# untitled.net
KiCad netlist of a schematic drawn in EAGLE
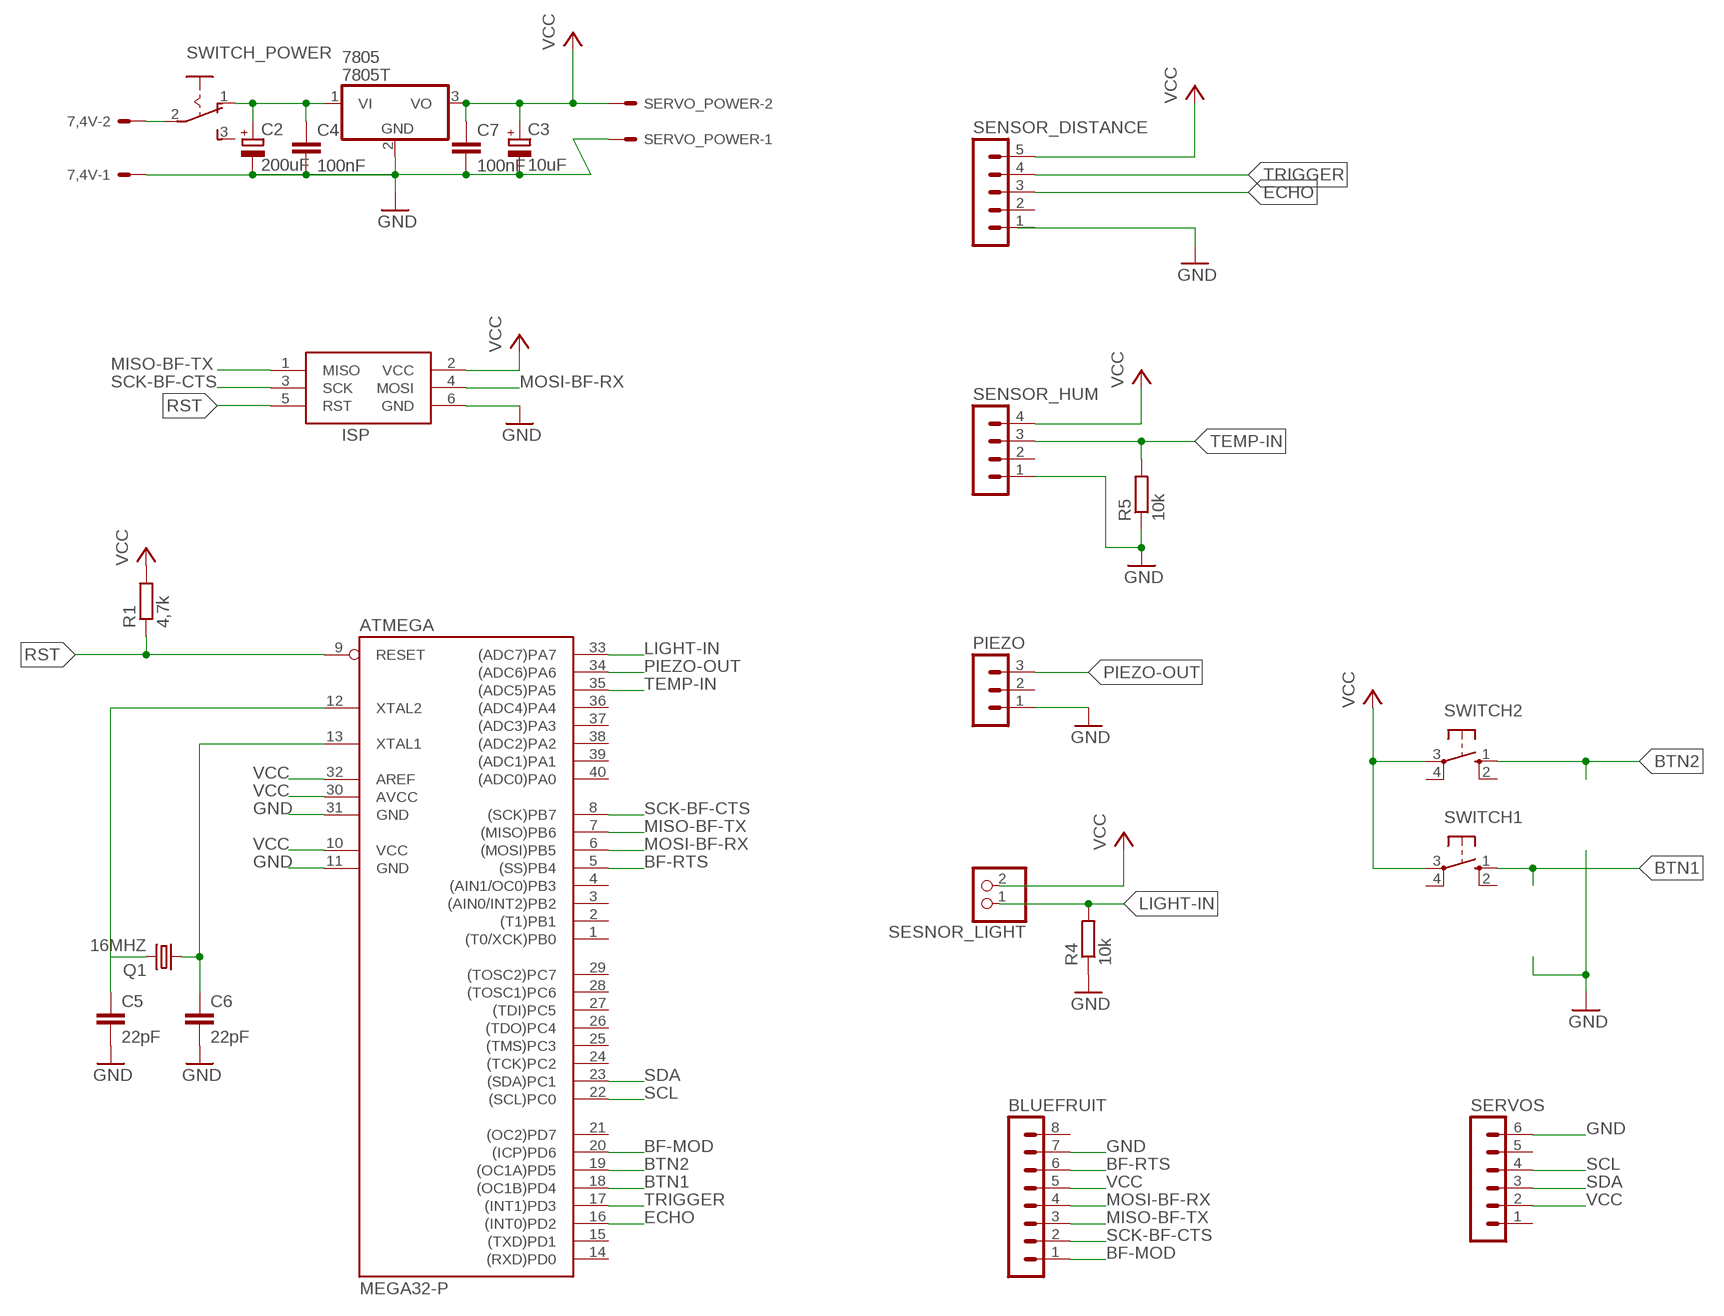
[diagram p0: schematic, sheet 1]

(export (version "E")
  (design (tool "Eeschema 10.0.6"))
  (components
    (comp (ref "7,4V")
      (value "KK-156-2")
      (footprint "eagle-import:KK-156-2")
      (libsource (lib "eagle-import") (part "KK-156-2"))
    )
    (comp (ref "7805")
      (value "7805T")
      (footprint "eagle-import:TO220H")
      (libsource (lib "eagle-import") (part "78T05"))
    )
    (comp (ref "ATMEGA")
      (value "MEGA32-P")
      (footprint "eagle-import:DIL40")
      (fields (field (name "MPN") "ATMEGA32-16PU"))
      (libsource (lib "eagle-import") (part "MEGA32-P"))
    )
    (comp (ref "BLUEFRUIT")
      (value "MA08-1")
      (footprint "eagle-import:MA08-1")
      (libsource (lib "eagle-import") (part "MA08-1"))
    )
    (comp (ref "C2")
      (value "200uF")
      (footprint "eagle-import:E5-10,5")
      (libsource (lib "eagle-import") (part "CPOL-EUE5-10.5"))
    )
    (comp (ref "C3")
      (value "10uF")
      (footprint "eagle-import:E5-10,5")
      (libsource (lib "eagle-import") (part "CPOL-EUE5-10.5"))
    )
    (comp (ref "C4")
      (value "100nF")
      (footprint "eagle-import:C025-025X050")
      (libsource (lib "eagle-import") (part "C-EU025-025X050"))
    )
    (comp (ref "C5")
      (value "22pF")
      (footprint "eagle-import:C025-025X050")
      (libsource (lib "eagle-import") (part "C-EU025-025X050"))
    )
    (comp (ref "C6")
      (value "22pF")
      (footprint "eagle-import:C025-025X050")
      (libsource (lib "eagle-import") (part "C-EU025-025X050"))
    )
    (comp (ref "C7")
      (value "100nF")
      (footprint "eagle-import:C025-025X050")
      (libsource (lib "eagle-import") (part "C-EU025-025X050"))
    )
    (comp (ref "ISP")
      (value "AVRISP-6")
      (footprint "eagle-import:AVRISP")
      (libsource (lib "eagle-import") (part "AVRISP-6"))
    )
    (comp (ref "PIEZO")
      (value "MA03-1")
      (footprint "eagle-import:MA03-1")
      (libsource (lib "eagle-import") (part "MA03-1"))
    )
    (comp (ref "Q1")
      (value "16MHZ")
      (footprint "eagle-import:HC49_S")
      (libsource (lib "eagle-import") (part "CRYSTALHC49S"))
    )
    (comp (ref "R1")
      (value "4,7k")
      (footprint "eagle-import:0207_10")
      (libsource (lib "eagle-import") (part "R-EU_0207/10"))
    )
    (comp (ref "R4")
      (value "10k")
      (footprint "eagle-import:0207_10")
      (libsource (lib "eagle-import") (part "R-EU_0207/10"))
    )
    (comp (ref "R5")
      (value "10k")
      (footprint "eagle-import:0207_10")
      (libsource (lib "eagle-import") (part "R-EU_0207/10"))
    )
    (comp (ref "SENSOR_DISTANCE")
      (value "MA05-1")
      (footprint "eagle-import:MA05-1")
      (libsource (lib "eagle-import") (part "MA05-1"))
    )
    (comp (ref "SENSOR_HUM")
      (value "MA04-1")
      (footprint "eagle-import:MA04-1")
      (libsource (lib "eagle-import") (part "MA04-1"))
    )
    (comp (ref "SERVOS")
      (value "MA06-1")
      (footprint "eagle-import:MA06-1")
      (libsource (lib "eagle-import") (part "MA06-1"))
    )
    (comp (ref "SERVO_POWER")
      (value "KK-156-2")
      (footprint "eagle-import:KK-156-2")
      (libsource (lib "eagle-import") (part "KK-156-2"))
    )
    (comp (ref "SESNOR_LIGHT")
      (value "PINHD-1X2")
      (footprint "eagle-import:1X02")
      (libsource (lib "eagle-import") (part "PINHD-1X2"))
    )
    (comp (ref "SWITCH1")
      (value "10-XX")
      (footprint "eagle-import:B3F-10XX")
      (fields (field (name "MPN") "B3F-1000"))
      (libsource (lib "eagle-import") (part "10-XX"))
    )
    (comp (ref "SWITCH2")
      (value "10-XX")
      (footprint "eagle-import:B3F-10XX")
      (fields (field (name "MPN") "B3F-1000"))
      (libsource (lib "eagle-import") (part "10-XX"))
    )
    (comp (ref "SWITCH_POWER")
      (value "255SB")
      (footprint "eagle-import:255SB")
      (libsource (lib "eagle-import") (part "255SB"))
    )
  )
  (nets
    (net (code "1") (name "/BF-MOD") (class "Default")
      (node (ref "ATMEGA") (pin "20") (pinfunction "(ICP)PD6_20") (pintype "bidirectional"))
      (node (ref "BLUEFRUIT") (pin "1") (pinfunction "1_1") (pintype "passive"))
    )
    (net (code "2") (name "/BF-RTS") (class "Default")
      (node (ref "ATMEGA") (pin "5") (pinfunction "(SS)PB4_5") (pintype "bidirectional"))
      (node (ref "BLUEFRUIT") (pin "6") (pinfunction "6_6") (pintype "passive"))
    )
    (net (code "3") (name "/MISO-BF-TX") (class "Default")
      (node (ref "ATMEGA") (pin "7") (pinfunction "(MISO)PB6_7") (pintype "bidirectional"))
      (node (ref "BLUEFRUIT") (pin "3") (pinfunction "3_3") (pintype "passive"))
      (node (ref "ISP") (pin "1") (pinfunction "MISO_1") (pintype "input"))
    )
    (net (code "4") (name "/MOSI-BF-RX") (class "Default")
      (node (ref "ATMEGA") (pin "6") (pinfunction "(MOSI)PB5_6") (pintype "bidirectional"))
      (node (ref "BLUEFRUIT") (pin "4") (pinfunction "4_4") (pintype "passive"))
      (node (ref "ISP") (pin "4") (pinfunction "MOSI_4") (pintype "output"))
    )
    (net (code "5") (name "/SCK-BF-CTS") (class "Default")
      (node (ref "ATMEGA") (pin "8") (pinfunction "(SCK)PB7_8") (pintype "bidirectional"))
      (node (ref "BLUEFRUIT") (pin "2") (pinfunction "2_2") (pintype "passive"))
      (node (ref "ISP") (pin "3") (pinfunction "SCK_3") (pintype "output"))
    )
    (net (code "6") (name "/SCL") (class "Default")
      (node (ref "ATMEGA") (pin "22") (pinfunction "(SCL)PC0_22") (pintype "bidirectional"))
      (node (ref "SERVOS") (pin "4") (pinfunction "4_4") (pintype "passive"))
    )
    (net (code "7") (name "/SDA") (class "Default")
      (node (ref "ATMEGA") (pin "23") (pinfunction "(SDA)PC1_23") (pintype "bidirectional"))
      (node (ref "SERVOS") (pin "3") (pinfunction "3_3") (pintype "passive"))
    )
    (net (code "8") (name "BTN1") (class "Default")
      (node (ref "ATMEGA") (pin "18") (pinfunction "(OC1B)PD4_18") (pintype "bidirectional"))
      (node (ref "SWITCH1") (pin "1") (pinfunction "S_1") (pintype "passive"))
    )
    (net (code "9") (name "BTN2") (class "Default")
      (node (ref "ATMEGA") (pin "19") (pinfunction "(OC1A)PD5_19") (pintype "bidirectional"))
      (node (ref "SWITCH2") (pin "1") (pinfunction "S_1") (pintype "passive"))
    )
    (net (code "10") (name "ECHO") (class "Default")
      (node (ref "ATMEGA") (pin "16") (pinfunction "(INT0)PD2_16") (pintype "bidirectional"))
      (node (ref "SENSOR_DISTANCE") (pin "3") (pinfunction "3_3") (pintype "passive"))
    )
    (net (code "11") (name "GND") (class "Default")
      (node (ref "7,4V") (pin "1") (pinfunction "S_1") (pintype "passive"))
      (node (ref "7805") (pin "2") (pinfunction "GND_2") (pintype "passive"))
      (node (ref "ATMEGA") (pin "11") (pinfunction "GND_11") (pintype "power_in"))
      (node (ref "ATMEGA") (pin "31") (pinfunction "GND_31") (pintype "power_in"))
      (node (ref "BLUEFRUIT") (pin "7") (pinfunction "7_7") (pintype "passive"))
      (node (ref "C2") (pin "-") (pinfunction "-_-") (pintype "passive"))
      (node (ref "C3") (pin "-") (pinfunction "-_-") (pintype "passive"))
      (node (ref "C4") (pin "2") (pinfunction "2_2") (pintype "passive"))
      (node (ref "C5") (pin "2") (pinfunction "2_2") (pintype "passive"))
      (node (ref "C6") (pin "2") (pinfunction "2_2") (pintype "passive"))
      (node (ref "C7") (pin "2") (pinfunction "2_2") (pintype "passive"))
      (node (ref "ISP") (pin "6") (pinfunction "GND_6") (pintype "power_in"))
      (node (ref "PIEZO") (pin "1") (pinfunction "1_1") (pintype "passive"))
      (node (ref "R4") (pin "1") (pinfunction "1_1") (pintype "passive"))
      (node (ref "R5") (pin "1") (pinfunction "1_1") (pintype "passive"))
      (node (ref "SENSOR_HUM") (pin "1") (pinfunction "1_1") (pintype "passive"))
      (node (ref "SERVOS") (pin "6") (pinfunction "6_6") (pintype "passive"))
      (node (ref "SERVO_POWER") (pin "1") (pinfunction "S_1") (pintype "passive"))
    )
    (net (code "12") (name "LIGHT-IN") (class "Default")
      (node (ref "ATMEGA") (pin "33") (pinfunction "(ADC7)PA7_33") (pintype "bidirectional"))
      (node (ref "R4") (pin "2") (pinfunction "2_2") (pintype "passive"))
      (node (ref "SESNOR_LIGHT") (pin "1") (pinfunction "1_1") (pintype "passive"))
    )
    (net (code "13") (name "Net-(7,4VB-S)") (class "Default")
      (node (ref "7,4V") (pin "2") (pinfunction "S_2") (pintype "passive"))
      (node (ref "SWITCH_POWER") (pin "2") (pinfunction "P_2") (pintype "passive"))
    )
    (net (code "14") (name "Net-(7805-VI)") (class "Default")
      (node (ref "7805") (pin "1") (pinfunction "VI_1") (pintype "input"))
      (node (ref "C2") (pin "+") (pinfunction "+_+") (pintype "passive"))
      (node (ref "C4") (pin "1") (pinfunction "1_1") (pintype "passive"))
      (node (ref "SWITCH_POWER") (pin "1") (pinfunction "O_1") (pintype "passive"))
    )
    (net (code "15") (name "Net-(ATMEGA-XTAL1)") (class "Default")
      (node (ref "ATMEGA") (pin "13") (pinfunction "XTAL1_13") (pintype "bidirectional"))
      (node (ref "C6") (pin "1") (pinfunction "1_1") (pintype "passive"))
      (node (ref "Q1") (pin "1") (pinfunction "1_1") (pintype "passive"))
    )
    (net (code "16") (name "Net-(ATMEGA-XTAL2)") (class "Default")
      (node (ref "ATMEGA") (pin "12") (pinfunction "XTAL2_12") (pintype "bidirectional"))
      (node (ref "C5") (pin "1") (pinfunction "1_1") (pintype "passive"))
      (node (ref "Q1") (pin "2") (pinfunction "2_2") (pintype "passive"))
    )
    (net (code "17") (name "PIEZO-OUT") (class "Default")
      (node (ref "ATMEGA") (pin "34") (pinfunction "(ADC6)PA6_34") (pintype "bidirectional"))
      (node (ref "PIEZO") (pin "3") (pinfunction "3_3") (pintype "passive"))
    )
    (net (code "18") (name "RST") (class "Default")
      (node (ref "ATMEGA") (pin "9") (pinfunction "RESET_9") (pintype "input"))
      (node (ref "ISP") (pin "5") (pinfunction "RST_5") (pintype "output"))
      (node (ref "R1") (pin "1") (pinfunction "1_1") (pintype "passive"))
    )
    (net (code "19") (name "TEMP-IN") (class "Default")
      (node (ref "ATMEGA") (pin "35") (pinfunction "(ADC5)PA5_35") (pintype "bidirectional"))
      (node (ref "R5") (pin "2") (pinfunction "2_2") (pintype "passive"))
      (node (ref "SENSOR_HUM") (pin "3") (pinfunction "3_3") (pintype "passive"))
    )
    (net (code "20") (name "TRIGGER") (class "Default")
      (node (ref "ATMEGA") (pin "17") (pinfunction "(INT1)PD3_17") (pintype "bidirectional"))
      (node (ref "SENSOR_DISTANCE") (pin "4") (pinfunction "4_4") (pintype "passive"))
    )
    (net (code "21") (name "VCC") (class "Default")
      (node (ref "7805") (pin "3") (pinfunction "VO_3") (pintype "passive"))
      (node (ref "ATMEGA") (pin "10") (pinfunction "VCC_10") (pintype "power_in"))
      (node (ref "ATMEGA") (pin "30") (pinfunction "AVCC_30") (pintype "power_in"))
      (node (ref "ATMEGA") (pin "32") (pinfunction "AREF_32") (pintype "passive"))
      (node (ref "BLUEFRUIT") (pin "5") (pinfunction "5_5") (pintype "passive"))
      (node (ref "C3") (pin "+") (pinfunction "+_+") (pintype "passive"))
      (node (ref "C7") (pin "1") (pinfunction "1_1") (pintype "passive"))
      (node (ref "ISP") (pin "2") (pinfunction "VCC_2") (pintype "power_in"))
      (node (ref "R1") (pin "2") (pinfunction "2_2") (pintype "passive"))
      (node (ref "SENSOR_DISTANCE") (pin "5") (pinfunction "5_5") (pintype "passive"))
      (node (ref "SENSOR_HUM") (pin "4") (pinfunction "4_4") (pintype "passive"))
      (node (ref "SERVOS") (pin "2") (pinfunction "2_2") (pintype "passive"))
      (node (ref "SERVO_POWER") (pin "2") (pinfunction "S_2") (pintype "passive"))
      (node (ref "SESNOR_LIGHT") (pin "2") (pinfunction "2_2") (pintype "passive"))
      (node (ref "SWITCH1") (pin "3") (pinfunction "P_3") (pintype "passive"))
      (node (ref "SWITCH2") (pin "3") (pinfunction "P_3") (pintype "passive"))
    )
    (net (code "22") (name "unconnected-(ATMEGA-(ADC0)PA0-Pad40)") (class "Default")
      (node (ref "ATMEGA") (pin "40") (pinfunction "(ADC0)PA0_40") (pintype "bidirectional"))
    )
    (net (code "23") (name "unconnected-(ATMEGA-(ADC1)PA1-Pad39)") (class "Default")
      (node (ref "ATMEGA") (pin "39") (pinfunction "(ADC1)PA1_39") (pintype "bidirectional"))
    )
    (net (code "24") (name "unconnected-(ATMEGA-(ADC2)PA2-Pad38)") (class "Default")
      (node (ref "ATMEGA") (pin "38") (pinfunction "(ADC2)PA2_38") (pintype "bidirectional"))
    )
    (net (code "25") (name "unconnected-(ATMEGA-(ADC3)PA3-Pad37)") (class "Default")
      (node (ref "ATMEGA") (pin "37") (pinfunction "(ADC3)PA3_37") (pintype "bidirectional"))
    )
    (net (code "26") (name "unconnected-(ATMEGA-(ADC4)PA4-Pad36)") (class "Default")
      (node (ref "ATMEGA") (pin "36") (pinfunction "(ADC4)PA4_36") (pintype "bidirectional"))
    )
    (net (code "27") (name "unconnected-(ATMEGA-(AIN0{slash}INT2)PB2-Pad3)") (class "Default")
      (node (ref "ATMEGA") (pin "3") (pinfunction "(AIN0/INT2)PB2_3") (pintype "bidirectional"))
    )
    (net (code "28") (name "unconnected-(ATMEGA-(AIN1{slash}OC0)PB3-Pad4)") (class "Default")
      (node (ref "ATMEGA") (pin "4") (pinfunction "(AIN1/OC0)PB3_4") (pintype "bidirectional"))
    )
    (net (code "29") (name "unconnected-(ATMEGA-(OC2)PD7-Pad21)") (class "Default")
      (node (ref "ATMEGA") (pin "21") (pinfunction "(OC2)PD7_21") (pintype "bidirectional"))
    )
    (net (code "30") (name "unconnected-(ATMEGA-(RXD)PD0-Pad14)") (class "Default")
      (node (ref "ATMEGA") (pin "14") (pinfunction "(RXD)PD0_14") (pintype "bidirectional"))
    )
    (net (code "31") (name "unconnected-(ATMEGA-(T0{slash}XCK)PB0-Pad1)") (class "Default")
      (node (ref "ATMEGA") (pin "1") (pinfunction "(T0/XCK)PB0_1") (pintype "bidirectional"))
    )
    (net (code "32") (name "unconnected-(ATMEGA-(T1)PB1-Pad2)") (class "Default")
      (node (ref "ATMEGA") (pin "2") (pinfunction "(T1)PB1_2") (pintype "bidirectional"))
    )
    (net (code "33") (name "unconnected-(ATMEGA-(TCK)PC2-Pad24)") (class "Default")
      (node (ref "ATMEGA") (pin "24") (pinfunction "(TCK)PC2_24") (pintype "bidirectional"))
    )
    (net (code "34") (name "unconnected-(ATMEGA-(TDI)PC5-Pad27)") (class "Default")
      (node (ref "ATMEGA") (pin "27") (pinfunction "(TDI)PC5_27") (pintype "bidirectional"))
    )
    (net (code "35") (name "unconnected-(ATMEGA-(TDO)PC4-Pad26)") (class "Default")
      (node (ref "ATMEGA") (pin "26") (pinfunction "(TDO)PC4_26") (pintype "bidirectional"))
    )
    (net (code "36") (name "unconnected-(ATMEGA-(TMS)PC3-Pad25)") (class "Default")
      (node (ref "ATMEGA") (pin "25") (pinfunction "(TMS)PC3_25") (pintype "bidirectional"))
    )
    (net (code "37") (name "unconnected-(ATMEGA-(TOSC1)PC6-Pad28)") (class "Default")
      (node (ref "ATMEGA") (pin "28") (pinfunction "(TOSC1)PC6_28") (pintype "bidirectional"))
    )
    (net (code "38") (name "unconnected-(ATMEGA-(TOSC2)PC7-Pad29)") (class "Default")
      (node (ref "ATMEGA") (pin "29") (pinfunction "(TOSC2)PC7_29") (pintype "bidirectional"))
    )
    (net (code "39") (name "unconnected-(ATMEGA-(TXD)PD1-Pad15)") (class "Default")
      (node (ref "ATMEGA") (pin "15") (pinfunction "(TXD)PD1_15") (pintype "bidirectional"))
    )
    (net (code "40") (name "unconnected-(BLUEFRUIT-Pad8)") (class "Default")
      (node (ref "BLUEFRUIT") (pin "8") (pinfunction "8_8") (pintype "passive"))
    )
    (net (code "41") (name "unconnected-(PIEZO-Pad2)") (class "Default")
      (node (ref "PIEZO") (pin "2") (pinfunction "2_2") (pintype "passive"))
    )
    (net (code "42") (name "unconnected-(SENSOR_DISTANCE-Pad1)") (class "Default")
      (node (ref "SENSOR_DISTANCE") (pin "1") (pinfunction "1_1") (pintype "passive"))
    )
    (net (code "43") (name "unconnected-(SENSOR_DISTANCE-Pad2)") (class "Default")
      (node (ref "SENSOR_DISTANCE") (pin "2") (pinfunction "2_2") (pintype "passive"))
    )
    (net (code "44") (name "unconnected-(SENSOR_HUM-Pad2)") (class "Default")
      (node (ref "SENSOR_HUM") (pin "2") (pinfunction "2_2") (pintype "passive"))
    )
    (net (code "45") (name "unconnected-(SERVOS-Pad1)") (class "Default")
      (node (ref "SERVOS") (pin "1") (pinfunction "1_1") (pintype "passive"))
    )
    (net (code "46") (name "unconnected-(SERVOS-Pad5)") (class "Default")
      (node (ref "SERVOS") (pin "5") (pinfunction "5_5") (pintype "passive"))
    )
    (net (code "47") (name "unconnected-(SWITCH1-P1-Pad4)") (class "Default")
      (node (ref "SWITCH1") (pin "4") (pinfunction "P1_4") (pintype "passive"))
    )
    (net (code "48") (name "unconnected-(SWITCH1-S1-Pad2)") (class "Default")
      (node (ref "SWITCH1") (pin "2") (pinfunction "S1_2") (pintype "passive"))
    )
    (net (code "49") (name "unconnected-(SWITCH2-P1-Pad4)") (class "Default")
      (node (ref "SWITCH2") (pin "4") (pinfunction "P1_4") (pintype "passive"))
    )
    (net (code "50") (name "unconnected-(SWITCH2-S1-Pad2)") (class "Default")
      (node (ref "SWITCH2") (pin "2") (pinfunction "S1_2") (pintype "passive"))
    )
    (net (code "51") (name "unconnected-(SWITCH_POWER-S-Pad3)") (class "Default")
      (node (ref "SWITCH_POWER") (pin "3") (pinfunction "S_3") (pintype "passive"))
    )
  )
)
